# AINx1.net
KiCad netlist of a schematic drawn in EAGLE
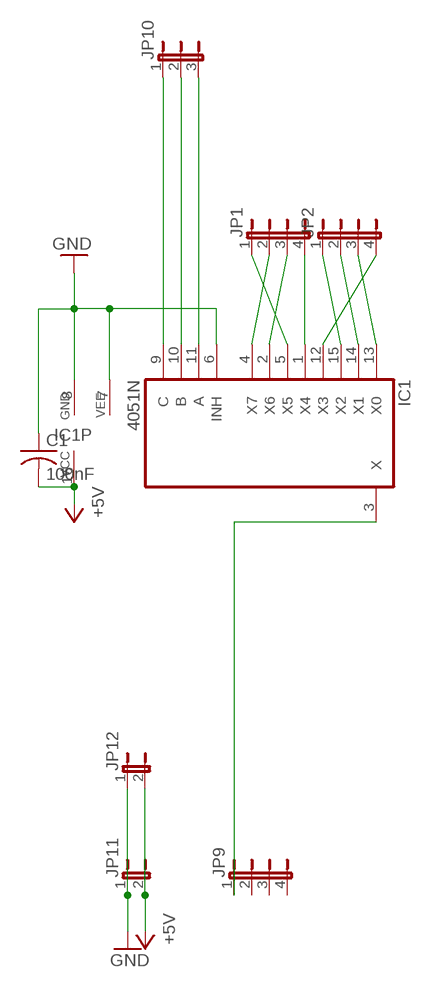
[diagram p0: schematic, sheet 1]

(export (version "E")
  (design (tool "Eeschema 10.0.6"))
  (components
    (comp (ref "C1")
      (value "100nF")
      (footprint "eagle-import:C025-025X050")
      (libsource (lib "eagle-import") (part "C-US025-025X050"))
    )
    (comp (ref "IC1")
      (value "4051N")
      (footprint "eagle-import:DIL16")
      (libsource (lib "eagle-import") (part "4051N"))
    )
    (comp (ref "JP1")
      (value "JP4E")
      (footprint "eagle-import:JP4")
      (libsource (lib "eagle-import") (part "JP4E"))
    )
    (comp (ref "JP2")
      (value "JP4E")
      (footprint "eagle-import:JP4")
      (libsource (lib "eagle-import") (part "JP4E"))
    )
    (comp (ref "JP9")
      (value "JP4E")
      (footprint "eagle-import:JP4")
      (libsource (lib "eagle-import") (part "JP4E"))
    )
    (comp (ref "JP10")
      (value "JP2E")
      (footprint "eagle-import:JP2")
      (libsource (lib "eagle-import") (part "JP2E"))
    )
    (comp (ref "JP11")
      (value "JP1E")
      (footprint "eagle-import:JP1")
      (libsource (lib "eagle-import") (part "JP1E"))
    )
    (comp (ref "JP12")
      (value "JP1E")
      (footprint "eagle-import:JP1")
      (libsource (lib "eagle-import") (part "JP1E"))
    )
  )
  (nets
    (net (code "1") (name "+5V") (class "Default")
      (node (ref "C1") (pin "2") (pinfunction "2_2") (pintype "passive"))
      (node (ref "IC1") (pin "16") (pinfunction "VCC_16") (pintype "power_in"))
      (node (ref "JP11") (pin "2") (pinfunction "2_2") (pintype "passive"))
      (node (ref "JP12") (pin "2") (pinfunction "2_2") (pintype "passive"))
    )
    (net (code "2") (name "GND") (class "Default")
      (node (ref "C1") (pin "1") (pinfunction "1_1") (pintype "passive"))
      (node (ref "IC1") (pin "6") (pinfunction "INH_6") (pintype "input"))
      (node (ref "IC1") (pin "7") (pinfunction "VEE_7") (pintype "power_in"))
      (node (ref "IC1") (pin "8") (pinfunction "GND_8") (pintype "power_in"))
      (node (ref "JP11") (pin "1") (pinfunction "1_1") (pintype "passive"))
      (node (ref "JP12") (pin "1") (pinfunction "1_1") (pintype "passive"))
    )
    (net (code "3") (name "Net-(IC1A-A)") (class "Default")
      (node (ref "IC1") (pin "11") (pinfunction "A_11") (pintype "input"))
      (node (ref "JP10") (pin "3") (pinfunction "3_3") (pintype "passive"))
    )
    (net (code "4") (name "Net-(IC1A-B)") (class "Default")
      (node (ref "IC1") (pin "10") (pinfunction "B_10") (pintype "input"))
      (node (ref "JP10") (pin "2") (pinfunction "2_2") (pintype "passive"))
    )
    (net (code "5") (name "Net-(IC1A-C)") (class "Default")
      (node (ref "IC1") (pin "9") (pinfunction "C_9") (pintype "input"))
      (node (ref "JP10") (pin "1") (pinfunction "1_1") (pintype "passive"))
    )
    (net (code "6") (name "Net-(IC1A-X)") (class "Default")
      (node (ref "IC1") (pin "3") (pinfunction "X_3") (pintype "bidirectional"))
      (node (ref "JP9") (pin "1") (pinfunction "1_1") (pintype "passive"))
    )
    (net (code "7") (name "Net-(IC1A-X0)") (class "Default")
      (node (ref "IC1") (pin "13") (pinfunction "X0_13") (pintype "bidirectional"))
      (node (ref "JP2") (pin "3") (pinfunction "3_3") (pintype "passive"))
    )
    (net (code "8") (name "Net-(IC1A-X1)") (class "Default")
      (node (ref "IC1") (pin "14") (pinfunction "X1_14") (pintype "bidirectional"))
      (node (ref "JP2") (pin "2") (pinfunction "2_2") (pintype "passive"))
    )
    (net (code "9") (name "Net-(IC1A-X2)") (class "Default")
      (node (ref "IC1") (pin "15") (pinfunction "X2_15") (pintype "bidirectional"))
      (node (ref "JP2") (pin "1") (pinfunction "1_1") (pintype "passive"))
    )
    (net (code "10") (name "Net-(IC1A-X3)") (class "Default")
      (node (ref "IC1") (pin "12") (pinfunction "X3_12") (pintype "bidirectional"))
      (node (ref "JP2") (pin "4") (pinfunction "4_4") (pintype "passive"))
    )
    (net (code "11") (name "Net-(IC1A-X4)") (class "Default")
      (node (ref "IC1") (pin "1") (pinfunction "X4_1") (pintype "bidirectional"))
      (node (ref "JP1") (pin "4") (pinfunction "4_4") (pintype "passive"))
    )
    (net (code "12") (name "Net-(IC1A-X5)") (class "Default")
      (node (ref "IC1") (pin "5") (pinfunction "X5_5") (pintype "bidirectional"))
      (node (ref "JP1") (pin "1") (pinfunction "1_1") (pintype "passive"))
    )
    (net (code "13") (name "Net-(IC1A-X6)") (class "Default")
      (node (ref "IC1") (pin "2") (pinfunction "X6_2") (pintype "bidirectional"))
      (node (ref "JP1") (pin "3") (pinfunction "3_3") (pintype "passive"))
    )
    (net (code "14") (name "Net-(IC1A-X7)") (class "Default")
      (node (ref "IC1") (pin "4") (pinfunction "X7_4") (pintype "bidirectional"))
      (node (ref "JP1") (pin "2") (pinfunction "2_2") (pintype "passive"))
    )
    (net (code "15") (name "unconnected-(JP9-Pad2)") (class "Default")
      (node (ref "JP9") (pin "2") (pinfunction "2_2") (pintype "passive"))
    )
    (net (code "16") (name "unconnected-(JP9-Pad3)") (class "Default")
      (node (ref "JP9") (pin "3") (pinfunction "3_3") (pintype "passive"))
    )
    (net (code "17") (name "unconnected-(JP9-Pad4)") (class "Default")
      (node (ref "JP9") (pin "4") (pinfunction "4_4") (pintype "passive"))
    )
  )
)
